# FPGA_Bank_0_Supplies.net
KiCad netlist of a schematic drawn in Altium Designer
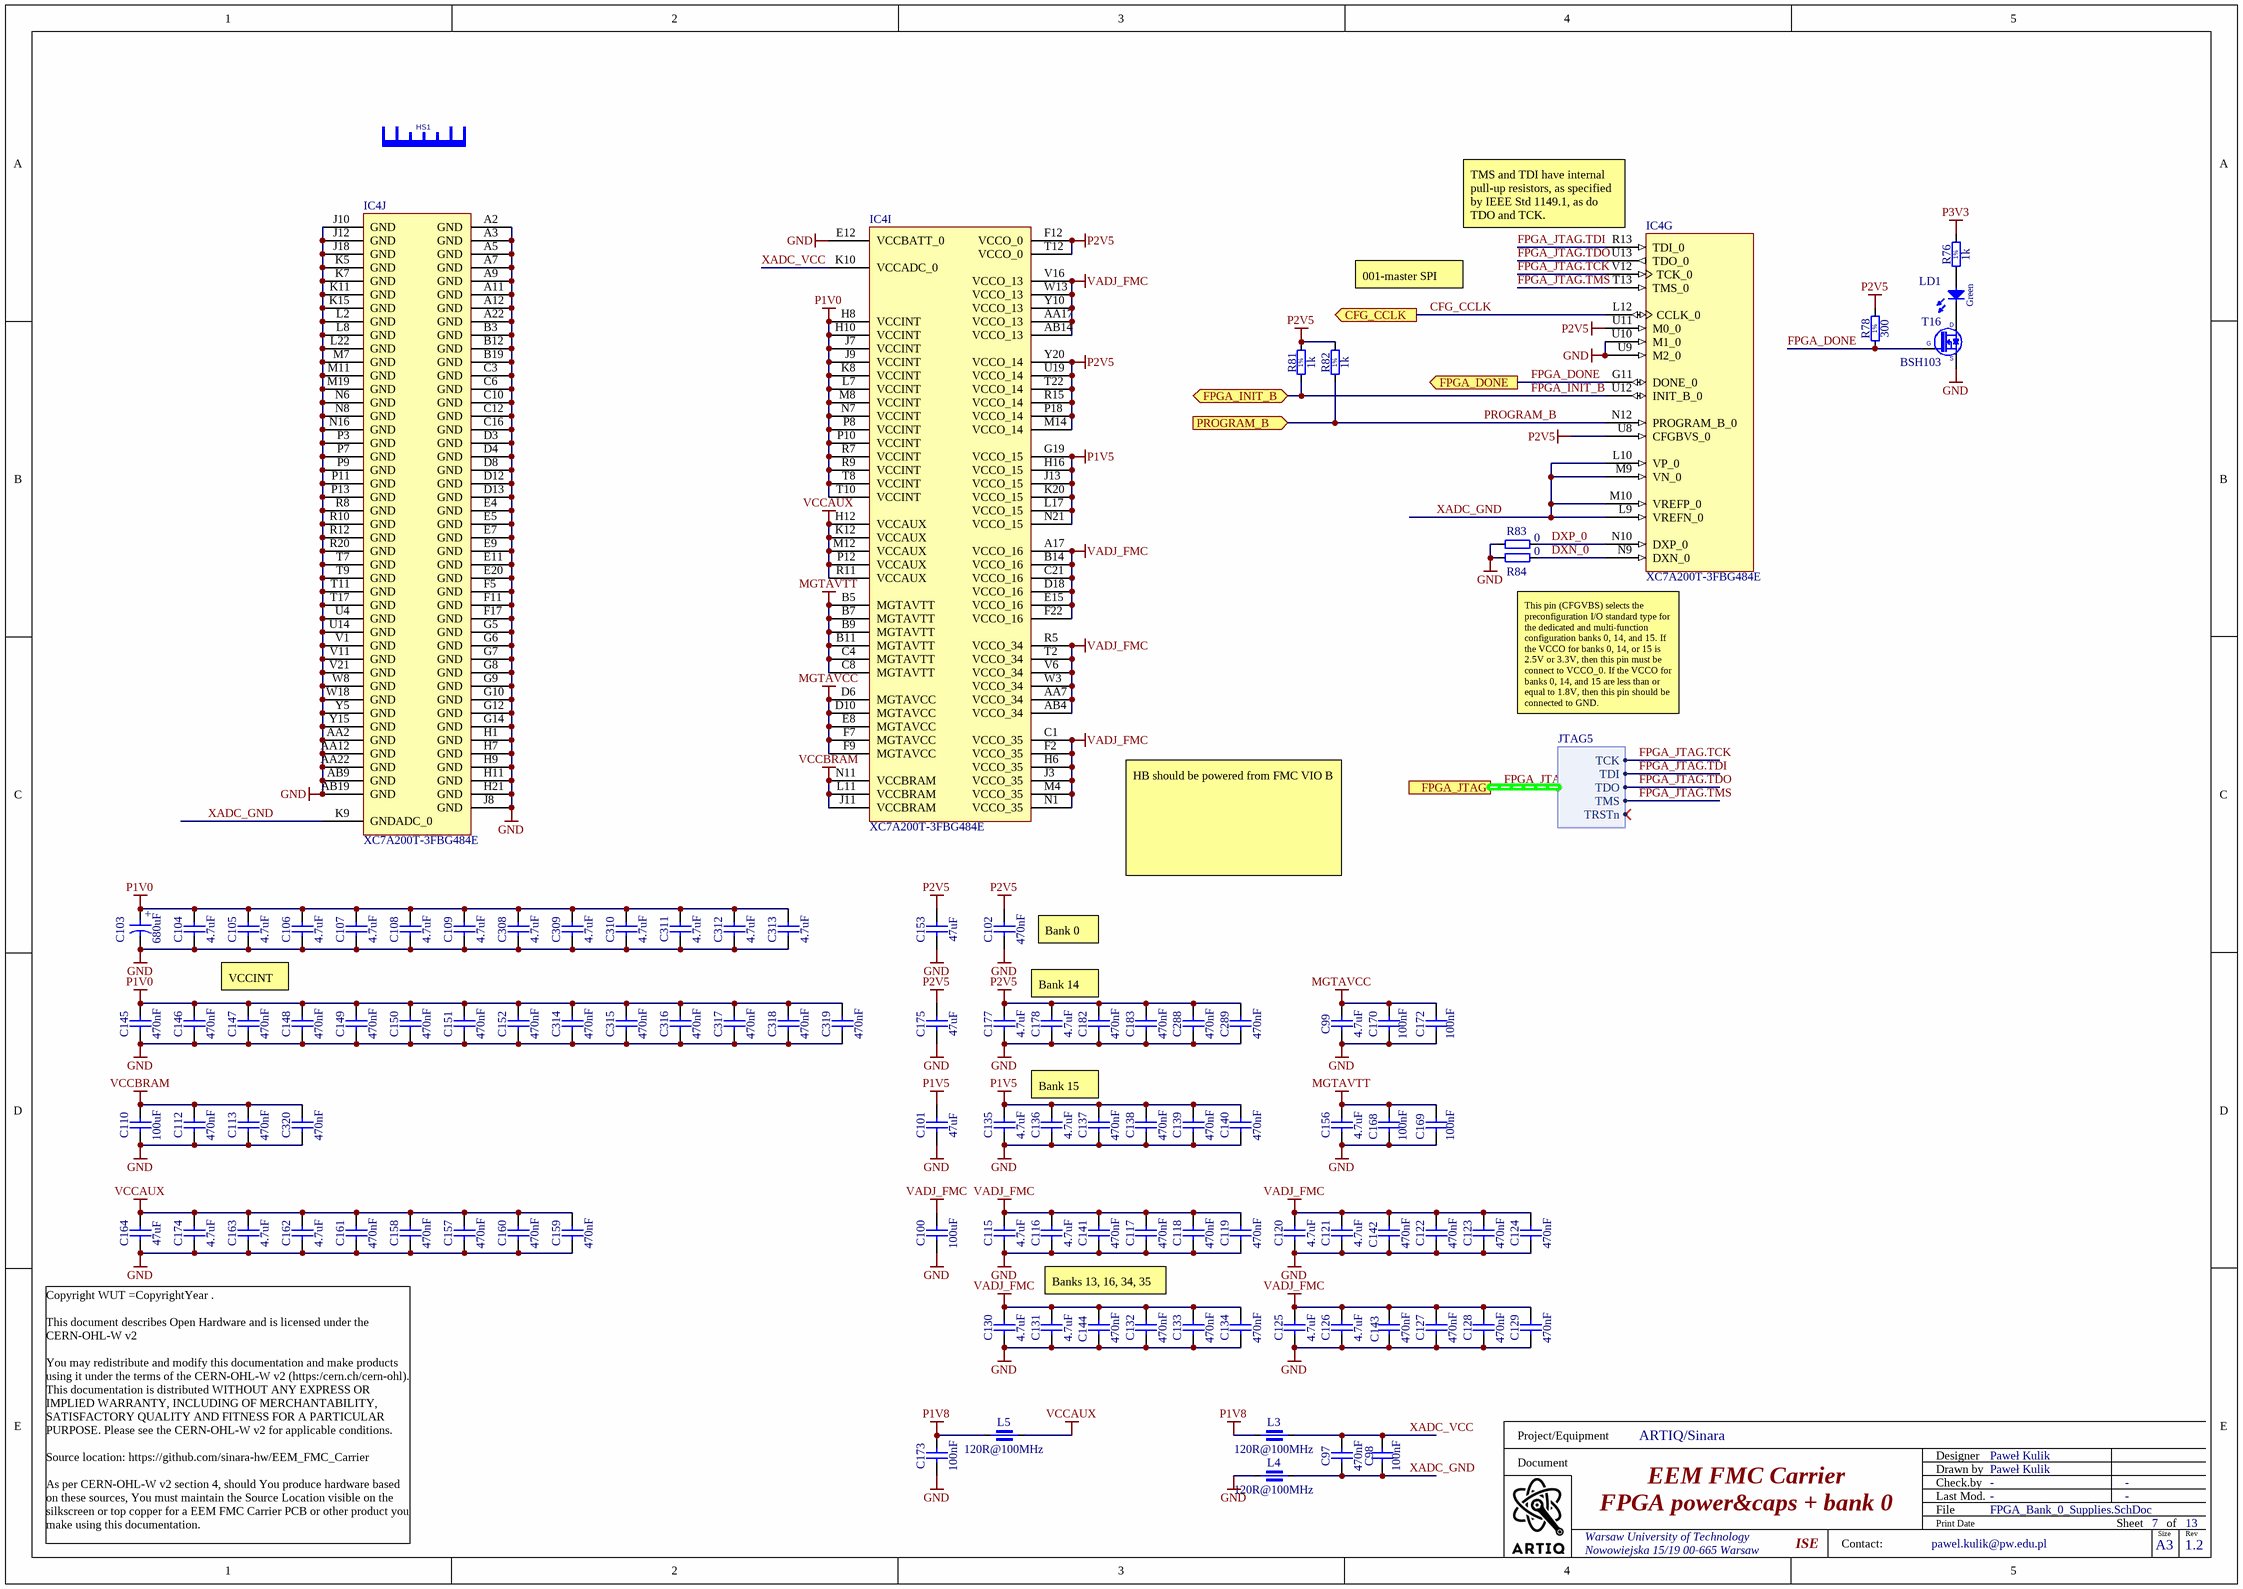
[diagram p0: FPGA_Bank_0_Supplies.SchDoc]

(export (version "E")
  (design (tool "Eeschema 10.0.6"))
  (components
    (comp (ref "C97")
      (value "470nF")
      (footprint "CAPC0603X33N")
      (description "Non-polarised capacitor")
      (fields
        (field (name "PART NUMBER") "CC0201_470NF_4V_20%_X5R")
        (field (name "VOLTAGE") "4V")
        (field (name "AUTHOR") "CERN DEM JLC")
      )
      (libsource (lib "Capacitors") (part "Capacitor - non polarized"))
    )
    (comp (ref "C98")
      (value "100nF")
      (footprint "CAPC0603X33N")
      (description "Non-polarised capacitor")
      (fields
        (field (name "PART NUMBER") "CC0201_100NF_6.3V_10%_X5R")
        (field (name "VOLTAGE") "6.3V")
        (field (name "AUTHOR") "CERN DEM JLC")
      )
      (libsource (lib "Capacitors") (part "Capacitor - non polarized"))
    )
    (comp (ref "C99")
      (value "4.7uF")
      (footprint "CAPC1005X55N")
      (description "Non-polarised capacitor")
      (fields
        (field (name "PART NUMBER") "CC0402_4.7UF_6.3V_20%_X5R")
        (field (name "VOLTAGE") "6.3V")
        (field (name "AUTHOR") "CERN DEM JLC")
      )
      (libsource (lib "Capacitors") (part "Capacitor - non polarized"))
    )
    (comp (ref "C100")
      (value "100uF")
      (footprint "CAPC3216X180N")
      (description "Non-polarised capacitor")
      (fields
        (field (name "PART NUMBER") "CC1206_100UF_6.3V_20%_X5R")
        (field (name "VOLTAGE") "6.3V")
        (field (name "AUTHOR") "CERN DEM JLC")
      )
      (libsource (lib "Capacitors") (part "Capacitor - non polarized"))
    )
    (comp (ref "C101")
      (value "47uF")
      (footprint "CAPC1608X100N")
      (description "Non-polarised capacitor")
      (fields
        (field (name "PART NUMBER") "CC0603_47UF_6.3V_20%_X5R")
        (field (name "VOLTAGE") "6.3V")
        (field (name "AUTHOR") "CERN DEM JLC")
      )
      (libsource (lib "Capacitors") (part "Capacitor - non polarized"))
    )
    (comp (ref "C102")
      (value "470nF")
      (footprint "CAPC0603X33N")
      (description "Non-polarised capacitor")
      (fields
        (field (name "PART NUMBER") "CC0201_470NF_4V_20%_X5R")
        (field (name "VOLTAGE") "4V")
        (field (name "AUTHOR") "CERN DEM JLC")
      )
      (libsource (lib "Capacitors") (part "Capacitor - non polarized"))
    )
    (comp (ref "C103")
      (value "680uF")
      (footprint "CAPMP7343X430N")
      (description "Polarised capacitor")
      (fields
        (field (name "PART NUMBER") "CTE7343-43_680UF_6.3V_10%_LESR0018_AVX_TPM")
        (field (name "VOLTAGE") "6.3V")
        (field (name "AUTHOR") "CERN DEM JLC")
      )
      (libsource (lib "Capacitors") (part "Capacitor - polarized"))
    )
    (comp (ref "C104")
      (value "4.7uF")
      (footprint "CAPC1005X55N")
      (description "Non-polarised capacitor")
      (fields
        (field (name "MANUFACTURER") "GENERIC")
        (field (name "PART NUMBER") "CC0402_4.7UF_6.3V_20%_X5R")
        (field (name "AUTHOR") "CERN DEM JLC")
      )
      (libsource (lib "Capacitors") (part "Capacitor - non polarized"))
    )
    (comp (ref "C105")
      (value "4.7uF")
      (footprint "CAPC1005X55N")
      (description "Non-polarised capacitor")
      (fields
        (field (name "MANUFACTURER") "GENERIC")
        (field (name "PART NUMBER") "CC0402_4.7UF_6.3V_20%_X5R")
        (field (name "AUTHOR") "CERN DEM JLC")
      )
      (libsource (lib "Capacitors") (part "Capacitor - non polarized"))
    )
    (comp (ref "C106")
      (value "4.7uF")
      (footprint "CAPC1005X55N")
      (description "Non-polarised capacitor")
      (fields
        (field (name "MANUFACTURER") "GENERIC")
        (field (name "PART NUMBER") "CC0402_4.7UF_6.3V_20%_X5R")
        (field (name "AUTHOR") "CERN DEM JLC")
      )
      (libsource (lib "Capacitors") (part "Capacitor - non polarized"))
    )
    (comp (ref "C107")
      (value "4.7uF")
      (footprint "CAPC1005X55N")
      (description "Non-polarised capacitor")
      (fields
        (field (name "MANUFACTURER") "GENERIC")
        (field (name "PART NUMBER") "CC0402_4.7UF_6.3V_20%_X5R")
        (field (name "AUTHOR") "CERN DEM JLC")
      )
      (libsource (lib "Capacitors") (part "Capacitor - non polarized"))
    )
    (comp (ref "C108")
      (value "4.7uF")
      (footprint "CAPC1005X55N")
      (description "Non-polarised capacitor")
      (fields
        (field (name "MANUFACTURER") "GENERIC")
        (field (name "PART NUMBER") "CC0402_4.7UF_6.3V_20%_X5R")
        (field (name "AUTHOR") "CERN DEM JLC")
      )
      (libsource (lib "Capacitors") (part "Capacitor - non polarized"))
    )
    (comp (ref "C109")
      (value "4.7uF")
      (footprint "CAPC1005X55N")
      (description "Non-polarised capacitor")
      (fields
        (field (name "MANUFACTURER") "GENERIC")
        (field (name "PART NUMBER") "CC0402_4.7UF_6.3V_20%_X5R")
        (field (name "AUTHOR") "CERN DEM JLC")
      )
      (libsource (lib "Capacitors") (part "Capacitor - non polarized"))
    )
    (comp (ref "C110")
      (value "100uF")
      (footprint "CAPC3216X180N")
      (description "Non-polarised capacitor")
      (fields
        (field (name "PART NUMBER") "CC1206_100UF_6.3V_20%_X5R")
        (field (name "VOLTAGE") "6.3V")
        (field (name "AUTHOR") "CERN DEM JLC")
      )
      (libsource (lib "Capacitors") (part "Capacitor - non polarized"))
    )
    (comp (ref "C112")
      (value "470nF")
      (footprint "CAPC0603X33N")
      (description "Non-polarised capacitor")
      (fields
        (field (name "PART NUMBER") "CC0201_470NF_4V_20%_X5R")
        (field (name "VOLTAGE") "4V")
        (field (name "AUTHOR") "CERN DEM JLC")
      )
      (libsource (lib "Capacitors") (part "Capacitor - non polarized"))
    )
    (comp (ref "C113")
      (value "470nF")
      (footprint "CAPC0603X33N")
      (description "Non-polarised capacitor")
      (fields
        (field (name "PART NUMBER") "CC0201_470NF_4V_20%_X5R")
        (field (name "VOLTAGE") "4V")
        (field (name "AUTHOR") "CERN DEM JLC")
      )
      (libsource (lib "Capacitors") (part "Capacitor - non polarized"))
    )
    (comp (ref "C115")
      (value "4.7uF")
      (footprint "CAPC1005X55N")
      (description "Non-polarised capacitor")
      (fields
        (field (name "MANUFACTURER") "GENERIC")
        (field (name "PART NUMBER") "CC0402_4.7UF_6.3V_20%_X5R")
        (field (name "AUTHOR") "CERN DEM JLC")
      )
      (libsource (lib "Capacitors") (part "Capacitor - non polarized"))
    )
    (comp (ref "C116")
      (value "4.7uF")
      (footprint "CAPC1005X55N")
      (description "Non-polarised capacitor")
      (fields
        (field (name "MANUFACTURER") "GENERIC")
        (field (name "PART NUMBER") "CC0402_4.7UF_6.3V_20%_X5R")
        (field (name "AUTHOR") "CERN DEM JLC")
      )
      (libsource (lib "Capacitors") (part "Capacitor - non polarized"))
    )
    (comp (ref "C117")
      (value "470nF")
      (footprint "CAPC0603X33N")
      (description "Non-polarised capacitor")
      (fields
        (field (name "PART NUMBER") "CC0201_470NF_4V_20%_X5R")
        (field (name "VOLTAGE") "4V")
        (field (name "AUTHOR") "CERN DEM JLC")
      )
      (libsource (lib "Capacitors") (part "Capacitor - non polarized"))
    )
    (comp (ref "C118")
      (value "470nF")
      (footprint "CAPC0603X33N")
      (description "Non-polarised capacitor")
      (fields
        (field (name "PART NUMBER") "CC0201_470NF_4V_20%_X5R")
        (field (name "VOLTAGE") "4V")
        (field (name "AUTHOR") "CERN DEM JLC")
      )
      (libsource (lib "Capacitors") (part "Capacitor - non polarized"))
    )
    (comp (ref "C119")
      (value "470nF")
      (footprint "CAPC0603X33N")
      (description "Non-polarised capacitor")
      (fields
        (field (name "PART NUMBER") "CC0201_470NF_4V_20%_X5R")
        (field (name "VOLTAGE") "4V")
        (field (name "AUTHOR") "CERN DEM JLC")
      )
      (libsource (lib "Capacitors") (part "Capacitor - non polarized"))
    )
    (comp (ref "C120")
      (value "4.7uF")
      (footprint "CAPC1005X55N")
      (description "Non-polarised capacitor")
      (fields
        (field (name "MANUFACTURER") "GENERIC")
        (field (name "PART NUMBER") "CC0402_4.7UF_6.3V_20%_X5R")
        (field (name "AUTHOR") "CERN DEM JLC")
      )
      (libsource (lib "Capacitors") (part "Capacitor - non polarized"))
    )
    (comp (ref "C121")
      (value "4.7uF")
      (footprint "CAPC1005X55N")
      (description "Non-polarised capacitor")
      (fields
        (field (name "MANUFACTURER") "GENERIC")
        (field (name "PART NUMBER") "CC0402_4.7UF_6.3V_20%_X5R")
        (field (name "AUTHOR") "CERN DEM JLC")
      )
      (libsource (lib "Capacitors") (part "Capacitor - non polarized"))
    )
    (comp (ref "C122")
      (value "470nF")
      (footprint "CAPC0603X33N")
      (description "Non-polarised capacitor")
      (fields
        (field (name "PART NUMBER") "CC0201_470NF_4V_20%_X5R")
        (field (name "VOLTAGE") "4V")
        (field (name "AUTHOR") "CERN DEM JLC")
      )
      (libsource (lib "Capacitors") (part "Capacitor - non polarized"))
    )
    (comp (ref "C123")
      (value "470nF")
      (footprint "CAPC0603X33N")
      (description "Non-polarised capacitor")
      (fields
        (field (name "PART NUMBER") "CC0201_470NF_4V_20%_X5R")
        (field (name "VOLTAGE") "4V")
        (field (name "AUTHOR") "CERN DEM JLC")
      )
      (libsource (lib "Capacitors") (part "Capacitor - non polarized"))
    )
    (comp (ref "C124")
      (value "470nF")
      (footprint "CAPC0603X33N")
      (description "Non-polarised capacitor")
      (fields
        (field (name "PART NUMBER") "CC0201_470NF_4V_20%_X5R")
        (field (name "VOLTAGE") "4V")
        (field (name "AUTHOR") "CERN DEM JLC")
      )
      (libsource (lib "Capacitors") (part "Capacitor - non polarized"))
    )
    (comp (ref "C125")
      (value "4.7uF")
      (footprint "CAPC1005X55N")
      (description "Non-polarised capacitor")
      (fields
        (field (name "MANUFACTURER") "GENERIC")
        (field (name "PART NUMBER") "CC0402_4.7UF_6.3V_20%_X5R")
        (field (name "AUTHOR") "CERN DEM JLC")
      )
      (libsource (lib "Capacitors") (part "Capacitor - non polarized"))
    )
    (comp (ref "C126")
      (value "4.7uF")
      (footprint "CAPC1005X55N")
      (description "Non-polarised capacitor")
      (fields
        (field (name "MANUFACTURER") "GENERIC")
        (field (name "PART NUMBER") "CC0402_4.7UF_6.3V_20%_X5R")
        (field (name "AUTHOR") "CERN DEM JLC")
      )
      (libsource (lib "Capacitors") (part "Capacitor - non polarized"))
    )
    (comp (ref "C127")
      (value "470nF")
      (footprint "CAPC0603X33N")
      (description "Non-polarised capacitor")
      (fields
        (field (name "PART NUMBER") "CC0201_470NF_4V_20%_X5R")
        (field (name "VOLTAGE") "4V")
        (field (name "AUTHOR") "CERN DEM JLC")
      )
      (libsource (lib "Capacitors") (part "Capacitor - non polarized"))
    )
    (comp (ref "C128")
      (value "470nF")
      (footprint "CAPC0603X33N")
      (description "Non-polarised capacitor")
      (fields
        (field (name "PART NUMBER") "CC0201_470NF_4V_20%_X5R")
        (field (name "VOLTAGE") "4V")
        (field (name "AUTHOR") "CERN DEM JLC")
      )
      (libsource (lib "Capacitors") (part "Capacitor - non polarized"))
    )
    (comp (ref "C129")
      (value "470nF")
      (footprint "CAPC0603X33N")
      (description "Non-polarised capacitor")
      (fields
        (field (name "PART NUMBER") "CC0201_470NF_4V_20%_X5R")
        (field (name "VOLTAGE") "4V")
        (field (name "AUTHOR") "CERN DEM JLC")
      )
      (libsource (lib "Capacitors") (part "Capacitor - non polarized"))
    )
    (comp (ref "C130")
      (value "4.7uF")
      (footprint "CAPC1005X55N")
      (description "Non-polarised capacitor")
      (fields
        (field (name "MANUFACTURER") "GENERIC")
        (field (name "PART NUMBER") "CC0402_4.7UF_6.3V_20%_X5R")
        (field (name "AUTHOR") "CERN DEM JLC")
      )
      (libsource (lib "Capacitors") (part "Capacitor - non polarized"))
    )
    (comp (ref "C131")
      (value "4.7uF")
      (footprint "CAPC1005X55N")
      (description "Non-polarised capacitor")
      (fields
        (field (name "MANUFACTURER") "GENERIC")
        (field (name "PART NUMBER") "CC0402_4.7UF_6.3V_20%_X5R")
        (field (name "AUTHOR") "CERN DEM JLC")
      )
      (libsource (lib "Capacitors") (part "Capacitor - non polarized"))
    )
    (comp (ref "C132")
      (value "470nF")
      (footprint "CAPC0603X33N")
      (description "Non-polarised capacitor")
      (fields
        (field (name "PART NUMBER") "CC0201_470NF_4V_20%_X5R")
        (field (name "VOLTAGE") "4V")
        (field (name "AUTHOR") "CERN DEM JLC")
      )
      (libsource (lib "Capacitors") (part "Capacitor - non polarized"))
    )
    (comp (ref "C133")
      (value "470nF")
      (footprint "CAPC0603X33N")
      (description "Non-polarised capacitor")
      (fields
        (field (name "PART NUMBER") "CC0201_470NF_4V_20%_X5R")
        (field (name "VOLTAGE") "4V")
        (field (name "AUTHOR") "CERN DEM JLC")
      )
      (libsource (lib "Capacitors") (part "Capacitor - non polarized"))
    )
    (comp (ref "C134")
      (value "470nF")
      (footprint "CAPC0603X33N")
      (description "Non-polarised capacitor")
      (fields
        (field (name "PART NUMBER") "CC0201_470NF_4V_20%_X5R")
        (field (name "VOLTAGE") "4V")
        (field (name "AUTHOR") "CERN DEM JLC")
      )
      (libsource (lib "Capacitors") (part "Capacitor - non polarized"))
    )
    (comp (ref "C135")
      (value "4.7uF")
      (footprint "CAPC1005X55N")
      (description "Non-polarised capacitor")
      (fields
        (field (name "MANUFACTURER") "GENERIC")
        (field (name "PART NUMBER") "CC0402_4.7UF_6.3V_20%_X5R")
        (field (name "AUTHOR") "CERN DEM JLC")
      )
      (libsource (lib "Capacitors") (part "Capacitor - non polarized"))
    )
    (comp (ref "C136")
      (value "4.7uF")
      (footprint "CAPC1005X55N")
      (description "Non-polarised capacitor")
      (fields
        (field (name "MANUFACTURER") "GENERIC")
        (field (name "PART NUMBER") "CC0402_4.7UF_6.3V_20%_X5R")
        (field (name "AUTHOR") "CERN DEM JLC")
      )
      (libsource (lib "Capacitors") (part "Capacitor - non polarized"))
    )
    (comp (ref "C137")
      (value "470nF")
      (footprint "CAPC0603X33N")
      (description "Non-polarised capacitor")
      (fields
        (field (name "PART NUMBER") "CC0201_470NF_4V_20%_X5R")
        (field (name "VOLTAGE") "4V")
        (field (name "AUTHOR") "CERN DEM JLC")
      )
      (libsource (lib "Capacitors") (part "Capacitor - non polarized"))
    )
    (comp (ref "C138")
      (value "470nF")
      (footprint "CAPC0603X33N")
      (description "Non-polarised capacitor")
      (fields
        (field (name "PART NUMBER") "CC0201_470NF_4V_20%_X5R")
        (field (name "VOLTAGE") "4V")
        (field (name "AUTHOR") "CERN DEM JLC")
      )
      (libsource (lib "Capacitors") (part "Capacitor - non polarized"))
    )
    (comp (ref "C139")
      (value "470nF")
      (footprint "CAPC0603X33N")
      (description "Non-polarised capacitor")
      (fields
        (field (name "PART NUMBER") "CC0201_470NF_4V_20%_X5R")
        (field (name "VOLTAGE") "4V")
        (field (name "AUTHOR") "CERN DEM JLC")
      )
      (libsource (lib "Capacitors") (part "Capacitor - non polarized"))
    )
    (comp (ref "C140")
      (value "470nF")
      (footprint "CAPC0603X33N")
      (description "Non-polarised capacitor")
      (fields
        (field (name "PART NUMBER") "CC0201_470NF_4V_20%_X5R")
        (field (name "VOLTAGE") "4V")
        (field (name "AUTHOR") "CERN DEM JLC")
      )
      (libsource (lib "Capacitors") (part "Capacitor - non polarized"))
    )
    (comp (ref "C141")
      (value "470nF")
      (footprint "CAPC0603X33N")
      (description "Non-polarised capacitor")
      (fields
        (field (name "PART NUMBER") "CC0201_470NF_4V_20%_X5R")
        (field (name "VOLTAGE") "4V")
        (field (name "AUTHOR") "CERN DEM JLC")
      )
      (libsource (lib "Capacitors") (part "Capacitor - non polarized"))
    )
    (comp (ref "C142")
      (value "470nF")
      (footprint "CAPC0603X33N")
      (description "Non-polarised capacitor")
      (fields
        (field (name "PART NUMBER") "CC0201_470NF_4V_20%_X5R")
        (field (name "VOLTAGE") "4V")
        (field (name "AUTHOR") "CERN DEM JLC")
      )
      (libsource (lib "Capacitors") (part "Capacitor - non polarized"))
    )
    (comp (ref "C143")
      (value "470nF")
      (footprint "CAPC0603X33N")
      (description "Non-polarised capacitor")
      (fields
        (field (name "PART NUMBER") "CC0201_470NF_4V_20%_X5R")
        (field (name "VOLTAGE") "4V")
        (field (name "AUTHOR") "CERN DEM JLC")
      )
      (libsource (lib "Capacitors") (part "Capacitor - non polarized"))
    )
    (comp (ref "C144")
      (value "470nF")
      (footprint "CAPC0603X33N")
      (description "Non-polarised capacitor")
      (fields
        (field (name "PART NUMBER") "CC0201_470NF_4V_20%_X5R")
        (field (name "VOLTAGE") "4V")
        (field (name "AUTHOR") "CERN DEM JLC")
      )
      (libsource (lib "Capacitors") (part "Capacitor - non polarized"))
    )
    (comp (ref "C145")
      (value "470nF")
      (footprint "CAPC0603X33N")
      (description "Non-polarised capacitor")
      (fields
        (field (name "PART NUMBER") "CC0201_470NF_4V_20%_X5R")
        (field (name "VOLTAGE") "4V")
        (field (name "AUTHOR") "CERN DEM JLC")
      )
      (libsource (lib "Capacitors") (part "Capacitor - non polarized"))
    )
    (comp (ref "C146")
      (value "470nF")
      (footprint "CAPC0603X33N")
      (description "Non-polarised capacitor")
      (fields
        (field (name "PART NUMBER") "CC0201_470NF_4V_20%_X5R")
        (field (name "VOLTAGE") "4V")
        (field (name "AUTHOR") "CERN DEM JLC")
      )
      (libsource (lib "Capacitors") (part "Capacitor - non polarized"))
    )
    (comp (ref "C147")
      (value "470nF")
      (footprint "CAPC0603X33N")
      (description "Non-polarised capacitor")
      (fields
        (field (name "PART NUMBER") "CC0201_470NF_4V_20%_X5R")
        (field (name "VOLTAGE") "4V")
        (field (name "AUTHOR") "CERN DEM JLC")
      )
      (libsource (lib "Capacitors") (part "Capacitor - non polarized"))
    )
    (comp (ref "C148")
      (value "470nF")
      (footprint "CAPC0603X33N")
      (description "Non-polarised capacitor")
      (fields
        (field (name "PART NUMBER") "CC0201_470NF_4V_20%_X5R")
        (field (name "VOLTAGE") "4V")
        (field (name "AUTHOR") "CERN DEM JLC")
      )
      (libsource (lib "Capacitors") (part "Capacitor - non polarized"))
    )
    (comp (ref "C149")
      (value "470nF")
      (footprint "CAPC0603X33N")
      (description "Non-polarised capacitor")
      (fields
        (field (name "PART NUMBER") "CC0201_470NF_4V_20%_X5R")
        (field (name "VOLTAGE") "4V")
        (field (name "AUTHOR") "CERN DEM JLC")
      )
      (libsource (lib "Capacitors") (part "Capacitor - non polarized"))
    )
    (comp (ref "C150")
      (value "470nF")
      (footprint "CAPC0603X33N")
      (description "Non-polarised capacitor")
      (fields
        (field (name "PART NUMBER") "CC0201_470NF_4V_20%_X5R")
        (field (name "VOLTAGE") "4V")
        (field (name "AUTHOR") "CERN DEM JLC")
      )
      (libsource (lib "Capacitors") (part "Capacitor - non polarized"))
    )
    (comp (ref "C151")
      (value "470nF")
      (footprint "CAPC0603X33N")
      (description "Non-polarised capacitor")
      (fields
        (field (name "PART NUMBER") "CC0201_470NF_4V_20%_X5R")
        (field (name "VOLTAGE") "4V")
        (field (name "AUTHOR") "CERN DEM JLC")
      )
      (libsource (lib "Capacitors") (part "Capacitor - non polarized"))
    )
    (comp (ref "C152")
      (value "470nF")
      (footprint "CAPC0603X33N")
      (description "Non-polarised capacitor")
      (fields
        (field (name "PART NUMBER") "CC0201_470NF_4V_20%_X5R")
        (field (name "VOLTAGE") "4V")
        (field (name "AUTHOR") "CERN DEM JLC")
      )
      (libsource (lib "Capacitors") (part "Capacitor - non polarized"))
    )
    (comp (ref "C153")
      (value "47uF")
      (footprint "CAPC1608X100N")
      (description "Non-polarised capacitor")
      (fields
        (field (name "PART NUMBER") "CC0603_47UF_6.3V_20%_X5R")
        (field (name "VOLTAGE") "6.3V")
        (field (name "AUTHOR") "CERN DEM JLC")
      )
      (libsource (lib "Capacitors") (part "Capacitor - non polarized"))
    )
    (comp (ref "C156")
      (value "4.7uF")
      (footprint "CAPC1005X55N")
      (description "Non-polarised capacitor")
      (fields
        (field (name "PART NUMBER") "CC0402_4.7UF_6.3V_20%_X5R")
        (field (name "VOLTAGE") "6.3V")
        (field (name "AUTHOR") "CERN DEM JLC")
      )
      (libsource (lib "Capacitors") (part "Capacitor - non polarized"))
    )
    (comp (ref "C157")
      (value "470nF")
      (footprint "CAPC0603X33N")
      (description "Non-polarised capacitor")
      (fields
        (field (name "PART NUMBER") "CC0201_470NF_4V_20%_X5R")
        (field (name "VOLTAGE") "4V")
        (field (name "AUTHOR") "CERN DEM JLC")
      )
      (libsource (lib "Capacitors") (part "Capacitor - non polarized"))
    )
    (comp (ref "C158")
      (value "470nF")
      (footprint "CAPC0603X33N")
      (description "Non-polarised capacitor")
      (fields
        (field (name "PART NUMBER") "CC0201_470NF_4V_20%_X5R")
        (field (name "VOLTAGE") "4V")
        (field (name "AUTHOR") "CERN DEM JLC")
      )
      (libsource (lib "Capacitors") (part "Capacitor - non polarized"))
    )
    (comp (ref "C159")
      (value "470nF")
      (footprint "CAPC0603X33N")
      (description "Non-polarised capacitor")
      (fields
        (field (name "PART NUMBER") "CC0201_470NF_4V_20%_X5R")
        (field (name "VOLTAGE") "4V")
        (field (name "AUTHOR") "CERN DEM JLC")
      )
      (libsource (lib "Capacitors") (part "Capacitor - non polarized"))
    )
    (comp (ref "C160")
      (value "470nF")
      (footprint "CAPC0603X33N")
      (description "Non-polarised capacitor")
      (fields
        (field (name "PART NUMBER") "CC0201_470NF_4V_20%_X5R")
        (field (name "VOLTAGE") "4V")
        (field (name "AUTHOR") "CERN DEM JLC")
      )
      (libsource (lib "Capacitors") (part "Capacitor - non polarized"))
    )
    (comp (ref "C161")
      (value "470nF")
      (footprint "CAPC0603X33N")
      (description "Non-polarised capacitor")
      (fields
        (field (name "PART NUMBER") "CC0201_470NF_4V_20%_X5R")
        (field (name "VOLTAGE") "4V")
        (field (name "AUTHOR") "CERN DEM JLC")
      )
      (libsource (lib "Capacitors") (part "Capacitor - non polarized"))
    )
    (comp (ref "C162")
      (value "4.7uF")
      (footprint "CAPC1005X55N")
      (description "Non-polarised capacitor")
      (fields
        (field (name "MANUFACTURER") "GENERIC")
        (field (name "PART NUMBER") "CC0402_4.7UF_6.3V_20%_X5R")
        (field (name "AUTHOR") "CERN DEM JLC")
      )
      (libsource (lib "Capacitors") (part "Capacitor - non polarized"))
    )
    (comp (ref "C163")
      (value "4.7uF")
      (footprint "CAPC1005X55N")
      (description "Non-polarised capacitor")
      (fields
        (field (name "MANUFACTURER") "GENERIC")
        (field (name "PART NUMBER") "CC0402_4.7UF_6.3V_20%_X5R")
        (field (name "AUTHOR") "CERN DEM JLC")
      )
      (libsource (lib "Capacitors") (part "Capacitor - non polarized"))
    )
    (comp (ref "C164")
      (value "47uF")
      (footprint "CAPC1608X100N")
      (description "Non-polarised capacitor")
      (fields
        (field (name "PART NUMBER") "CC0603_47UF_6.3V_20%_X5R")
        (field (name "VOLTAGE") "6.3V")
        (field (name "AUTHOR") "CERN DEM JLC")
      )
      (libsource (lib "Capacitors") (part "Capacitor - non polarized"))
    )
    (comp (ref "C168")
      (value "100nF")
      (footprint "CAPC0603X33N")
      (description "Non-polarised capacitor")
      (fields
        (field (name "PART NUMBER") "CC0201_100NF_6.3V_10%_X5R")
        (field (name "VOLTAGE") "6.3V")
        (field (name "AUTHOR") "CERN DEM JLC")
      )
      (libsource (lib "Capacitors") (part "Capacitor - non polarized"))
    )
    (comp (ref "C169")
      (value "100nF")
      (footprint "CAPC0603X33N")
      (description "Non-polarised capacitor")
      (fields
        (field (name "PART NUMBER") "CC0201_100NF_6.3V_10%_X5R")
        (field (name "VOLTAGE") "6.3V")
        (field (name "AUTHOR") "CERN DEM JLC")
      )
      (libsource (lib "Capacitors") (part "Capacitor - non polarized"))
    )
    (comp (ref "C170")
      (value "100nF")
      (footprint "CAPC0603X33N")
      (description "Non-polarised capacitor")
      (fields
        (field (name "PART NUMBER") "CC0201_100NF_6.3V_10%_X5R")
        (field (name "VOLTAGE") "6.3V")
        (field (name "AUTHOR") "CERN DEM JLC")
      )
      (libsource (lib "Capacitors") (part "Capacitor - non polarized"))
    )
    (comp (ref "C172")
      (value "100nF")
      (footprint "CAPC0603X33N")
      (description "Non-polarised capacitor")
      (fields
        (field (name "PART NUMBER") "CC0201_100NF_6.3V_10%_X5R")
        (field (name "VOLTAGE") "6.3V")
        (field (name "AUTHOR") "CERN DEM JLC")
      )
      (libsource (lib "Capacitors") (part "Capacitor - non polarized"))
    )
    (comp (ref "C173")
      (value "100nF")
      (footprint "CAPC0603X33N")
      (description "Non-polarised capacitor")
      (fields
        (field (name "PART NUMBER") "CC0201_100NF_6.3V_10%_X5R")
        (field (name "VOLTAGE") "6.3V")
        (field (name "AUTHOR") "CERN DEM JLC")
      )
      (libsource (lib "Capacitors") (part "Capacitor - non polarized"))
    )
    (comp (ref "C174")
      (value "4.7uF")
      (footprint "CAPC1005X55N")
      (description "Non-polarised capacitor")
      (fields
        (field (name "PART NUMBER") "CC0402_4.7UF_6.3V_20%_X5R")
        (field (name "VOLTAGE") "6.3V")
        (field (name "AUTHOR") "CERN DEM JLC")
      )
      (libsource (lib "Capacitors") (part "Capacitor - non polarized"))
    )
    (comp (ref "C175")
      (value "47uF")
      (footprint "CAPC1608X100N")
      (description "Non-polarised capacitor")
      (fields
        (field (name "PART NUMBER") "CC0603_47UF_6.3V_20%_X5R")
        (field (name "VOLTAGE") "6.3V")
        (field (name "AUTHOR") "CERN DEM JLC")
      )
      (libsource (lib "Capacitors") (part "Capacitor - non polarized"))
    )
    (comp (ref "C177")
      (value "4.7uF")
      (footprint "CAPC1005X55N")
      (description "Non-polarised capacitor")
      (fields
        (field (name "MANUFACTURER") "GENERIC")
        (field (name "PART NUMBER") "CC0402_4.7UF_6.3V_20%_X5R")
        (field (name "AUTHOR") "CERN DEM JLC")
      )
      (libsource (lib "Capacitors") (part "Capacitor - non polarized"))
    )
    (comp (ref "C178")
      (value "4.7uF")
      (footprint "CAPC1005X55N")
      (description "Non-polarised capacitor")
      (fields
        (field (name "MANUFACTURER") "GENERIC")
        (field (name "PART NUMBER") "CC0402_4.7UF_6.3V_20%_X5R")
        (field (name "AUTHOR") "CERN DEM JLC")
      )
      (libsource (lib "Capacitors") (part "Capacitor - non polarized"))
    )
    (comp (ref "C182")
      (value "470nF")
      (footprint "CAPC0603X33N")
      (description "Non-polarised capacitor")
      (fields
        (field (name "PART NUMBER") "CC0201_470NF_4V_20%_X5R")
        (field (name "VOLTAGE") "4V")
        (field (name "AUTHOR") "CERN DEM JLC")
      )
      (libsource (lib "Capacitors") (part "Capacitor - non polarized"))
    )
    (comp (ref "C183")
      (value "470nF")
      (footprint "CAPC0603X33N")
      (description "Non-polarised capacitor")
      (fields
        (field (name "PART NUMBER") "CC0201_470NF_4V_20%_X5R")
        (field (name "VOLTAGE") "4V")
        (field (name "AUTHOR") "CERN DEM JLC")
      )
      (libsource (lib "Capacitors") (part "Capacitor - non polarized"))
    )
    (comp (ref "C288")
      (value "470nF")
      (footprint "CAPC0603X33N")
      (description "Non-polarised capacitor")
      (fields
        (field (name "PART NUMBER") "CC0201_470NF_4V_20%_X5R")
        (field (name "VOLTAGE") "4V")
        (field (name "AUTHOR") "CERN DEM JLC")
      )
      (libsource (lib "Capacitors") (part "Capacitor - non polarized"))
    )
    (comp (ref "C289")
      (value "470nF")
      (footprint "CAPC0603X33N")
      (description "Non-polarised capacitor")
      (fields
        (field (name "PART NUMBER") "CC0201_470NF_4V_20%_X5R")
        (field (name "VOLTAGE") "4V")
        (field (name "AUTHOR") "CERN DEM JLC")
      )
      (libsource (lib "Capacitors") (part "Capacitor - non polarized"))
    )
    (comp (ref "C308")
      (value "4.7uF")
      (footprint "CAPC1005X55N")
      (description "Non-polarised capacitor")
      (fields
        (field (name "MANUFACTURER") "GENERIC")
        (field (name "PART NUMBER") "CC0402_4.7UF_6.3V_20%_X5R")
        (field (name "AUTHOR") "CERN DEM JLC")
      )
      (libsource (lib "Capacitors") (part "Capacitor - non polarized"))
    )
    (comp (ref "C309")
      (value "4.7uF")
      (footprint "CAPC1005X55N")
      (description "Non-polarised capacitor")
      (fields
        (field (name "MANUFACTURER") "GENERIC")
        (field (name "PART NUMBER") "CC0402_4.7UF_6.3V_20%_X5R")
        (field (name "AUTHOR") "CERN DEM JLC")
      )
      (libsource (lib "Capacitors") (part "Capacitor - non polarized"))
    )
    (comp (ref "C310")
      (value "4.7uF")
      (footprint "CAPC1005X55N")
      (description "Non-polarised capacitor")
      (fields
        (field (name "MANUFACTURER") "GENERIC")
        (field (name "PART NUMBER") "CC0402_4.7UF_6.3V_20%_X5R")
        (field (name "AUTHOR") "CERN DEM JLC")
      )
      (libsource (lib "Capacitors") (part "Capacitor - non polarized"))
    )
    (comp (ref "C311")
      (value "4.7uF")
      (footprint "CAPC1005X55N")
      (description "Non-polarised capacitor")
      (fields
        (field (name "MANUFACTURER") "GENERIC")
        (field (name "PART NUMBER") "CC0402_4.7UF_6.3V_20%_X5R")
        (field (name "AUTHOR") "CERN DEM JLC")
      )
      (libsource (lib "Capacitors") (part "Capacitor - non polarized"))
    )
    (comp (ref "C312")
      (value "4.7uF")
      (footprint "CAPC1005X55N")
      (description "Non-polarised capacitor")
      (fields
        (field (name "MANUFACTURER") "GENERIC")
        (field (name "PART NUMBER") "CC0402_4.7UF_6.3V_20%_X5R")
        (field (name "AUTHOR") "CERN DEM JLC")
      )
      (libsource (lib "Capacitors") (part "Capacitor - non polarized"))
    )
    (comp (ref "C313")
      (value "4.7uF")
      (footprint "CAPC1005X55N")
      (description "Non-polarised capacitor")
      (fields
        (field (name "MANUFACTURER") "GENERIC")
        (field (name "PART NUMBER") "CC0402_4.7UF_6.3V_20%_X5R")
        (field (name "AUTHOR") "CERN DEM JLC")
      )
      (libsource (lib "Capacitors") (part "Capacitor - non polarized"))
    )
    (comp (ref "C314")
      (value "470nF")
      (footprint "CAPC0603X33N")
      (description "Non-polarised capacitor")
      (fields
        (field (name "PART NUMBER") "CC0201_470NF_4V_20%_X5R")
        (field (name "VOLTAGE") "4V")
        (field (name "AUTHOR") "CERN DEM JLC")
      )
      (libsource (lib "Capacitors") (part "Capacitor - non polarized"))
    )
    (comp (ref "C315")
      (value "470nF")
      (footprint "CAPC0603X33N")
      (description "Non-polarised capacitor")
      (fields
        (field (name "PART NUMBER") "CC0201_470NF_4V_20%_X5R")
        (field (name "VOLTAGE") "4V")
        (field (name "AUTHOR") "CERN DEM JLC")
      )
      (libsource (lib "Capacitors") (part "Capacitor - non polarized"))
    )
    (comp (ref "C316")
      (value "470nF")
      (footprint "CAPC0603X33N")
      (description "Non-polarised capacitor")
      (fields
        (field (name "PART NUMBER") "CC0201_470NF_4V_20%_X5R")
        (field (name "VOLTAGE") "4V")
        (field (name "AUTHOR") "CERN DEM JLC")
      )
      (libsource (lib "Capacitors") (part "Capacitor - non polarized"))
    )
    (comp (ref "C317")
      (value "470nF")
      (footprint "CAPC0603X33N")
      (description "Non-polarised capacitor")
      (fields
        (field (name "PART NUMBER") "CC0201_470NF_4V_20%_X5R")
        (field (name "VOLTAGE") "4V")
        (field (name "AUTHOR") "CERN DEM JLC")
      )
      (libsource (lib "Capacitors") (part "Capacitor - non polarized"))
    )
    (comp (ref "C318")
      (value "470nF")
      (footprint "CAPC0603X33N")
      (description "Non-polarised capacitor")
      (fields
        (field (name "PART NUMBER") "CC0201_470NF_4V_20%_X5R")
        (field (name "VOLTAGE") "4V")
        (field (name "AUTHOR") "CERN DEM JLC")
      )
      (libsource (lib "Capacitors") (part "Capacitor - non polarized"))
    )
    (comp (ref "C319")
      (value "470nF")
      (footprint "CAPC0603X33N")
      (description "Non-polarised capacitor")
      (fields
        (field (name "PART NUMBER") "CC0201_470NF_4V_20%_X5R")
        (field (name "VOLTAGE") "4V")
        (field (name "AUTHOR") "CERN DEM JLC")
      )
      (libsource (lib "Capacitors") (part "Capacitor - non polarized"))
    )
    (comp (ref "C320")
      (value "470nF")
      (footprint "CAPC0603X33N")
      (description "Non-polarised capacitor")
      (fields
        (field (name "PART NUMBER") "CC0201_470NF_4V_20%_X5R")
        (field (name "VOLTAGE") "4V")
        (field (name "AUTHOR") "CERN DEM JLC")
      )
      (libsource (lib "Capacitors") (part "Capacitor - non polarized"))
    )
    (comp (ref "HS1")
      (value "RADIAN_FI23")
      (footprint "RADIAN_FI23")
      (description "Heat Sink Without Pad")
      (fields
        (field (name "MANUFACTURER") "Radian Thermal Products, Inc.")
        (field (name "MANUFACTURER PART NUMBER") "FI23+BU+T725")
      )
      (libsource (lib "Schlib1") (part "RADIAN_FI23"))
    )
    (comp (ref "IC4")
      (value "XC7A200T-3FBG484E")
      (footprint "BGA484C100P22X22_2300X2300X254")
      (description "Artix-7 FPGA, 285 User I/Os, 4 GTP, 484-Ball BGA, Pb-Free")
      (libsource (lib "Integrated_Library_LOADER") (part "XC7A200T-3FBG484E"))
    )
    (comp (ref "L3")
      (value "120R@100MHz")
      (footprint "INDC1608X65N")
      (fields
        (field (name "PART NUMBER") "IND0603_MURATA_BLM18SG121TN1D")
        (field (name "POWER") "3A")
        (field (name "MANUFACTURER") "MURATA")
        (field (name "AUTHOR") "CERN DEM JLC")
      )
      (libsource (lib "Inductors & Transformers") (part "Ferrite Bead"))
    )
    (comp (ref "L4")
      (value "120R@100MHz")
      (footprint "INDC1608X65N")
      (fields
        (field (name "PART NUMBER") "IND0603_MURATA_BLM18SG121TN1D")
        (field (name "POWER") "3A")
        (field (name "MANUFACTURER") "MURATA")
        (field (name "AUTHOR") "CERN DEM JLC")
      )
      (libsource (lib "Inductors & Transformers") (part "Ferrite Bead"))
    )
    (comp (ref "L5")
      (value "120R@100MHz")
      (footprint "INDC1608X65N")
      (fields
        (field (name "PART NUMBER") "IND0603_MURATA_BLM18SG121TN1D")
        (field (name "POWER") "3A")
        (field (name "MANUFACTURER") "MURATA")
        (field (name "AUTHOR") "CERN DEM JLC")
      )
      (libsource (lib "Inductors & Transformers") (part "Ferrite Bead"))
    )
    (comp (ref "LD1")
      (value "Green")
      (footprint "LED_KINGBRIGHT_KPH-1608CGCK")
      (description "LED Green 1C 2A")
      (fields
        (field (name "MANUFACTURER PART NUMBER") "KPH-1608CGCK")
        (field (name "PART NUMBER") "LED_KINGBRIGHT_KPH-1608CGCK")
        (field (name "AUTHOR") "CERN DEM JLC")
      )
      (libsource (lib "ICs And Semiconductors") (part "LED Green 1C 2A"))
    )
    (comp (ref "R76")
      (value "1k")
      (footprint "RESC1005X40N")
      (description "Resistor - 1%")
      (fields
        (field (name "PART NUMBER") "R0402_1K_1%_0.0625W_100PPM")
        (field (name "POWER") "0.0625W")
        (field (name "AUTHOR") "CERN DEM JLC")
      )
      (libsource (lib "Resistors") (part "Resistor - 1%"))
    )
    (comp (ref "R78")
      (value "300")
      (footprint "RESC1005X40N")
      (description "Resistor - 1%")
      (fields
        (field (name "PART NUMBER") "R0402_300R_1%_0.0625W_100PPM")
        (field (name "POWER") "0.0625W")
        (field (name "AUTHOR") "CERN DEM JLC")
      )
      (libsource (lib "Resistors") (part "Resistor - 1%"))
    )
    (comp (ref "R81")
      (value "1k")
      (footprint "RESC1005X40N")
      (description "Resistor - 1%")
      (fields
        (field (name "PART NUMBER") "R0402_1K_1%_0.0625W_100PPM")
        (field (name "POWER") "0.0625W")
        (field (name "AUTHOR") "CERN DEM JLC")
      )
      (libsource (lib "Resistors") (part "Resistor - 1%"))
    )
    (comp (ref "R82")
      (value "1k")
      (footprint "RESC1005X40N")
      (description "Resistor - 1%")
      (fields
        (field (name "PART NUMBER") "R0402_1K_1%_0.0625W_100PPM")
        (field (name "POWER") "0.0625W")
        (field (name "AUTHOR") "CERN DEM JLC")
      )
      (libsource (lib "Resistors") (part "Resistor - 1%"))
    )
    (comp (ref "R83")
      (value "0")
      (footprint "RESC0603X28N")
      (description "Resistor")
      (fields
        (field (name "PART NUMBER") "R0201_0R_JUMPER")
        (field (name "MANUFACTURER") "GENERIC")
        (field (name "AUTHOR") "CERN DEM JLC")
      )
      (libsource (lib "Resistors") (part "Resistor"))
    )
    (comp (ref "R84")
      (value "0")
      (footprint "RESC0603X28N")
      (description "Resistor")
      (fields
        (field (name "PART NUMBER") "R0201_0R_JUMPER")
        (field (name "MANUFACTURER") "GENERIC")
        (field (name "AUTHOR") "CERN DEM JLC")
      )
      (libsource (lib "Resistors") (part "Resistor"))
    )
    (comp (ref "T16")
      (value "BSH103")
      (footprint "SOT95P230X110-3N")
      (description "N-CHANNEL MOSFET WITH DIODE")
      (fields (field (name "MANUFACTURER") "NEXPERIA") (field (name "AUTHOR") "CERN DEM JLC"))
      (libsource (lib "ICs And Semiconductors") (part "N-MOSFET-D 1G 2S 3D"))
    )
  )
  (nets
    (net (code "2") (name "/CFG_CCLK") (class "Default")
      (node (ref "IC4") (pin "L12") (pinfunction "CCLK_0_L12") (pintype "bidirectional"))
    )
    (net (code "3") (name "/DXN_0") (class "Default")
      (node (ref "IC4") (pin "N9") (pinfunction "DXN_0_N9") (pintype "input"))
      (node (ref "R84") (pin "2") (pinfunction "2_2") (pintype "passive"))
    )
    (net (code "4") (name "/DXP_0") (class "Default")
      (node (ref "IC4") (pin "N10") (pinfunction "DXP_0_N10") (pintype "input"))
      (node (ref "R83") (pin "2") (pinfunction "2_2") (pintype "passive"))
    )
    (net (code "5") (name "/FPGA_DONE") (class "Default")
      (node (ref "IC4") (pin "G11") (pinfunction "DONE_0_G11") (pintype "bidirectional"))
      (node (ref "R78") (pin "1") (pinfunction "1_1") (pintype "passive"))
      (node (ref "T16") (pin "1") (pinfunction "G_1") (pintype "passive"))
    )
    (net (code "6") (name "/FPGA_INIT_B") (class "Default")
      (node (ref "IC4") (pin "U12") (pinfunction "INIT_B_0_U12") (pintype "bidirectional"))
      (node (ref "R81") (pin "1") (pinfunction "1_1") (pintype "passive"))
    )
    (net (code "7") (name "/FPGA_JTAG.TCK") (class "Default")
      (node (ref "IC4") (pin "V12") (pinfunction "TCK_0_V12") (pintype "input"))
    )
    (net (code "8") (name "/FPGA_JTAG.TDI") (class "Default")
      (node (ref "IC4") (pin "R13") (pinfunction "TDI_0_R13") (pintype "input"))
    )
    (net (code "9") (name "/FPGA_JTAG.TDO") (class "Default")
      (node (ref "IC4") (pin "U13") (pinfunction "TDO_0_U13") (pintype "output"))
    )
    (net (code "10") (name "/FPGA_JTAG.TMS") (class "Default")
      (node (ref "IC4") (pin "T13") (pinfunction "TMS_0_T13") (pintype "input"))
    )
    (net (code "12") (name "/PROGRAM_B") (class "Default")
      (node (ref "IC4") (pin "N12") (pinfunction "PROGRAM_B_0_N12") (pintype "input"))
      (node (ref "R82") (pin "1") (pinfunction "1_1") (pintype "passive"))
    )
    (net (code "13") (name "/XADC_GND") (class "Default")
      (node (ref "C97") (pin "1") (pinfunction "1_1") (pintype "passive"))
      (node (ref "C98") (pin "1") (pinfunction "1_1") (pintype "passive"))
      (node (ref "IC4") (pin "K9") (pinfunction "GNDADC_0_K9") (pintype "power_in"))
      (node (ref "IC4") (pin "L10") (pinfunction "VP_0_L10") (pintype "input"))
      (node (ref "IC4") (pin "L9") (pinfunction "VREFN_0_L9") (pintype "input"))
      (node (ref "IC4") (pin "M10") (pinfunction "VREFP_0_M10") (pintype "input"))
      (node (ref "IC4") (pin "M9") (pinfunction "VN_0_M9") (pintype "input"))
      (node (ref "L4") (pin "2") (pinfunction "2_2") (pintype "passive"))
    )
    (net (code "14") (name "/XADC_VCC") (class "Default")
      (node (ref "C97") (pin "2") (pinfunction "2_2") (pintype "passive"))
      (node (ref "C98") (pin "2") (pinfunction "2_2") (pintype "passive"))
      (node (ref "IC4") (pin "K10") (pinfunction "VCCADC_0_K10") (pintype "power_in"))
      (node (ref "L3") (pin "2") (pinfunction "2_2") (pintype "passive"))
    )
    (net (code "15") (name "GND") (class "Default")
      (node (ref "C100") (pin "1") (pinfunction "1_1") (pintype "passive"))
      (node (ref "C101") (pin "1") (pinfunction "1_1") (pintype "passive"))
      (node (ref "C102") (pin "1") (pinfunction "1_1") (pintype "passive"))
      (node (ref "C103") (pin "2") (pinfunction "2_2") (pintype "passive"))
      (node (ref "C104") (pin "1") (pinfunction "1_1") (pintype "passive"))
      (node (ref "C105") (pin "1") (pinfunction "1_1") (pintype "passive"))
      (node (ref "C106") (pin "1") (pinfunction "1_1") (pintype "passive"))
      (node (ref "C107") (pin "1") (pinfunction "1_1") (pintype "passive"))
      (node (ref "C108") (pin "1") (pinfunction "1_1") (pintype "passive"))
      (node (ref "C109") (pin "1") (pinfunction "1_1") (pintype "passive"))
      (node (ref "C110") (pin "1") (pinfunction "1_1") (pintype "passive"))
      (node (ref "C112") (pin "1") (pinfunction "1_1") (pintype "passive"))
      (node (ref "C113") (pin "1") (pinfunction "1_1") (pintype "passive"))
      (node (ref "C115") (pin "1") (pinfunction "1_1") (pintype "passive"))
      (node (ref "C116") (pin "1") (pinfunction "1_1") (pintype "passive"))
      (node (ref "C117") (pin "1") (pinfunction "1_1") (pintype "passive"))
      (node (ref "C118") (pin "1") (pinfunction "1_1") (pintype "passive"))
      (node (ref "C119") (pin "1") (pinfunction "1_1") (pintype "passive"))
      (node (ref "C120") (pin "1") (pinfunction "1_1") (pintype "passive"))
      (node (ref "C121") (pin "1") (pinfunction "1_1") (pintype "passive"))
      (node (ref "C122") (pin "1") (pinfunction "1_1") (pintype "passive"))
      (node (ref "C123") (pin "1") (pinfunction "1_1") (pintype "passive"))
      (node (ref "C124") (pin "1") (pinfunction "1_1") (pintype "passive"))
      (node (ref "C125") (pin "1") (pinfunction "1_1") (pintype "passive"))
      (node (ref "C126") (pin "1") (pinfunction "1_1") (pintype "passive"))
      (node (ref "C127") (pin "1") (pinfunction "1_1") (pintype "passive"))
      (node (ref "C128") (pin "1") (pinfunction "1_1") (pintype "passive"))
      (node (ref "C129") (pin "1") (pinfunction "1_1") (pintype "passive"))
      (node (ref "C130") (pin "1") (pinfunction "1_1") (pintype "passive"))
      (node (ref "C131") (pin "1") (pinfunction "1_1") (pintype "passive"))
      (node (ref "C132") (pin "1") (pinfunction "1_1") (pintype "passive"))
      (node (ref "C133") (pin "1") (pinfunction "1_1") (pintype "passive"))
      (node (ref "C134") (pin "1") (pinfunction "1_1") (pintype "passive"))
      (node (ref "C135") (pin "1") (pinfunction "1_1") (pintype "passive"))
      (node (ref "C136") (pin "1") (pinfunction "1_1") (pintype "passive"))
      (node (ref "C137") (pin "1") (pinfunction "1_1") (pintype "passive"))
      (node (ref "C138") (pin "1") (pinfunction "1_1") (pintype "passive"))
      (node (ref "C139") (pin "1") (pinfunction "1_1") (pintype "passive"))
      (node (ref "C140") (pin "1") (pinfunction "1_1") (pintype "passive"))
      (node (ref "C141") (pin "1") (pinfunction "1_1") (pintype "passive"))
      (node (ref "C142") (pin "1") (pinfunction "1_1") (pintype "passive"))
      (node (ref "C143") (pin "1") (pinfunction "1_1") (pintype "passive"))
      (node (ref "C144") (pin "1") (pinfunction "1_1") (pintype "passive"))
      (node (ref "C145") (pin "1") (pinfunction "1_1") (pintype "passive"))
      (node (ref "C146") (pin "1") (pinfunction "1_1") (pintype "passive"))
      (node (ref "C147") (pin "1") (pinfunction "1_1") (pintype "passive"))
      (node (ref "C148") (pin "1") (pinfunction "1_1") (pintype "passive"))
      (node (ref "C149") (pin "1") (pinfunction "1_1") (pintype "passive"))
      (node (ref "C150") (pin "1") (pinfunction "1_1") (pintype "passive"))
      (node (ref "C151") (pin "1") (pinfunction "1_1") (pintype "passive"))
      (node (ref "C152") (pin "1") (pinfunction "1_1") (pintype "passive"))
      (node (ref "C153") (pin "1") (pinfunction "1_1") (pintype "passive"))
      (node (ref "C156") (pin "1") (pinfunction "1_1") (pintype "passive"))
      (node (ref "C157") (pin "1") (pinfunction "1_1") (pintype "passive"))
      (node (ref "C158") (pin "1") (pinfunction "1_1") (pintype "passive"))
      (node (ref "C159") (pin "1") (pinfunction "1_1") (pintype "passive"))
      (node (ref "C160") (pin "1") (pinfunction "1_1") (pintype "passive"))
      (node (ref "C161") (pin "1") (pinfunction "1_1") (pintype "passive"))
      (node (ref "C162") (pin "1") (pinfunction "1_1") (pintype "passive"))
      (node (ref "C163") (pin "1") (pinfunction "1_1") (pintype "passive"))
      (node (ref "C164") (pin "1") (pinfunction "1_1") (pintype "passive"))
      (node (ref "C168") (pin "1") (pinfunction "1_1") (pintype "passive"))
      (node (ref "C169") (pin "1") (pinfunction "1_1") (pintype "passive"))
      (node (ref "C170") (pin "1") (pinfunction "1_1") (pintype "passive"))
      (node (ref "C172") (pin "1") (pinfunction "1_1") (pintype "passive"))
      (node (ref "C173") (pin "1") (pinfunction "1_1") (pintype "passive"))
      (node (ref "C174") (pin "1") (pinfunction "1_1") (pintype "passive"))
      (node (ref "C175") (pin "1") (pinfunction "1_1") (pintype "passive"))
      (node (ref "C177") (pin "1") (pinfunction "1_1") (pintype "passive"))
      (node (ref "C178") (pin "1") (pinfunction "1_1") (pintype "passive"))
      (node (ref "C182") (pin "1") (pinfunction "1_1") (pintype "passive"))
      (node (ref "C183") (pin "1") (pinfunction "1_1") (pintype "passive"))
      (node (ref "C288") (pin "1") (pinfunction "1_1") (pintype "passive"))
      (node (ref "C289") (pin "1") (pinfunction "1_1") (pintype "passive"))
      (node (ref "C308") (pin "1") (pinfunction "1_1") (pintype "passive"))
      (node (ref "C309") (pin "1") (pinfunction "1_1") (pintype "passive"))
      (node (ref "C310") (pin "1") (pinfunction "1_1") (pintype "passive"))
      (node (ref "C311") (pin "1") (pinfunction "1_1") (pintype "passive"))
      (node (ref "C312") (pin "1") (pinfunction "1_1") (pintype "passive"))
      (node (ref "C313") (pin "1") (pinfunction "1_1") (pintype "passive"))
      (node (ref "C314") (pin "1") (pinfunction "1_1") (pintype "passive"))
      (node (ref "C315") (pin "1") (pinfunction "1_1") (pintype "passive"))
      (node (ref "C316") (pin "1") (pinfunction "1_1") (pintype "passive"))
      (node (ref "C317") (pin "1") (pinfunction "1_1") (pintype "passive"))
      (node (ref "C318") (pin "1") (pinfunction "1_1") (pintype "passive"))
      (node (ref "C319") (pin "1") (pinfunction "1_1") (pintype "passive"))
      (node (ref "C320") (pin "1") (pinfunction "1_1") (pintype "passive"))
      (node (ref "C99") (pin "1") (pinfunction "1_1") (pintype "passive"))
      (node (ref "IC4") (pin "A11") (pinfunction "GND_A11") (pintype "power_in"))
      (node (ref "IC4") (pin "A12") (pinfunction "GND_A12") (pintype "power_in"))
      (node (ref "IC4") (pin "A2") (pinfunction "GND_A2") (pintype "power_in"))
      (node (ref "IC4") (pin "A22") (pinfunction "GND_A22") (pintype "power_in"))
      (node (ref "IC4") (pin "A3") (pinfunction "GND_A3") (pintype "power_in"))
      (node (ref "IC4") (pin "A5") (pinfunction "GND_A5") (pintype "power_in"))
      (node (ref "IC4") (pin "A7") (pinfunction "GND_A7") (pintype "power_in"))
      (node (ref "IC4") (pin "A9") (pinfunction "GND_A9") (pintype "power_in"))
      (node (ref "IC4") (pin "AA12") (pinfunction "GND_AA12") (pintype "power_in"))
      (node (ref "IC4") (pin "AA2") (pinfunction "GND_AA2") (pintype "power_in"))
      (node (ref "IC4") (pin "AA22") (pinfunction "GND_AA22") (pintype "power_in"))
      (node (ref "IC4") (pin "AB19") (pinfunction "GND_AB19") (pintype "power_in"))
      (node (ref "IC4") (pin "AB9") (pinfunction "GND_AB9") (pintype "power_in"))
      (node (ref "IC4") (pin "B12") (pinfunction "GND_B12") (pintype "power_in"))
      (node (ref "IC4") (pin "B19") (pinfunction "GND_B19") (pintype "power_in"))
      (node (ref "IC4") (pin "B3") (pinfunction "GND_B3") (pintype "power_in"))
      (node (ref "IC4") (pin "C10") (pinfunction "GND_C10") (pintype "power_in"))
      (node (ref "IC4") (pin "C12") (pinfunction "GND_C12") (pintype "power_in"))
      (node (ref "IC4") (pin "C16") (pinfunction "GND_C16") (pintype "power_in"))
      (node (ref "IC4") (pin "C3") (pinfunction "GND_C3") (pintype "power_in"))
      (node (ref "IC4") (pin "C6") (pinfunction "GND_C6") (pintype "power_in"))
      (node (ref "IC4") (pin "D12") (pinfunction "GND_D12") (pintype "power_in"))
      (node (ref "IC4") (pin "D13") (pinfunction "GND_D13") (pintype "power_in"))
      (node (ref "IC4") (pin "D3") (pinfunction "GND_D3") (pintype "power_in"))
      (node (ref "IC4") (pin "D4") (pinfunction "GND_D4") (pintype "power_in"))
      (node (ref "IC4") (pin "D8") (pinfunction "GND_D8") (pintype "power_in"))
      (node (ref "IC4") (pin "E11") (pinfunction "GND_E11") (pintype "power_in"))
      (node (ref "IC4") (pin "E12") (pinfunction "VCCBATT_0_E12") (pintype "power_in"))
      (node (ref "IC4") (pin "E20") (pinfunction "GND_E20") (pintype "power_in"))
      (node (ref "IC4") (pin "E4") (pinfunction "GND_E4") (pintype "power_in"))
      (node (ref "IC4") (pin "E5") (pinfunction "GND_E5") (pintype "power_in"))
      (node (ref "IC4") (pin "E7") (pinfunction "GND_E7") (pintype "power_in"))
      (node (ref "IC4") (pin "E9") (pinfunction "GND_E9") (pintype "power_in"))
      (node (ref "IC4") (pin "F11") (pinfunction "GND_F11") (pintype "power_in"))
      (node (ref "IC4") (pin "F17") (pinfunction "GND_F17") (pintype "power_in"))
      (node (ref "IC4") (pin "F5") (pinfunction "GND_F5") (pintype "power_in"))
      (node (ref "IC4") (pin "G10") (pinfunction "GND_G10") (pintype "power_in"))
      (node (ref "IC4") (pin "G12") (pinfunction "GND_G12") (pintype "power_in"))
      (node (ref "IC4") (pin "G14") (pinfunction "GND_G14") (pintype "power_in"))
      (node (ref "IC4") (pin "G5") (pinfunction "GND_G5") (pintype "power_in"))
      (node (ref "IC4") (pin "G6") (pinfunction "GND_G6") (pintype "power_in"))
      (node (ref "IC4") (pin "G7") (pinfunction "GND_G7") (pintype "power_in"))
      (node (ref "IC4") (pin "G8") (pinfunction "GND_G8") (pintype "power_in"))
      (node (ref "IC4") (pin "G9") (pinfunction "GND_G9") (pintype "power_in"))
      (node (ref "IC4") (pin "H1") (pinfunction "GND_H1") (pintype "power_in"))
      (node (ref "IC4") (pin "H11") (pinfunction "GND_H11") (pintype "power_in"))
      (node (ref "IC4") (pin "H21") (pinfunction "GND_H21") (pintype "power_in"))
      (node (ref "IC4") (pin "H7") (pinfunction "GND_H7") (pintype "power_in"))
      (node (ref "IC4") (pin "H9") (pinfunction "GND_H9") (pintype "power_in"))
      (node (ref "IC4") (pin "J10") (pinfunction "GND_J10") (pintype "power_in"))
      (node (ref "IC4") (pin "J12") (pinfunction "GND_J12") (pintype "power_in"))
      (node (ref "IC4") (pin "J18") (pinfunction "GND_J18") (pintype "power_in"))
      (node (ref "IC4") (pin "J8") (pinfunction "GND_J8") (pintype "power_in"))
      (node (ref "IC4") (pin "K11") (pinfunction "GND_K11") (pintype "power_in"))
      (node (ref "IC4") (pin "K15") (pinfunction "GND_K15") (pintype "power_in"))
      (node (ref "IC4") (pin "K5") (pinfunction "GND_K5") (pintype "power_in"))
      (node (ref "IC4") (pin "K7") (pinfunction "GND_K7") (pintype "power_in"))
      (node (ref "IC4") (pin "L2") (pinfunction "GND_L2") (pintype "power_in"))
      (node (ref "IC4") (pin "L22") (pinfunction "GND_L22") (pintype "power_in"))
      (node (ref "IC4") (pin "L8") (pinfunction "GND_L8") (pintype "power_in"))
      (node (ref "IC4") (pin "M11") (pinfunction "GND_M11") (pintype "power_in"))
      (node (ref "IC4") (pin "M19") (pinfunction "GND_M19") (pintype "power_in"))
      (node (ref "IC4") (pin "M7") (pinfunction "GND_M7") (pintype "power_in"))
      (node (ref "IC4") (pin "N16") (pinfunction "GND_N16") (pintype "power_in"))
      (node (ref "IC4") (pin "N6") (pinfunction "GND_N6") (pintype "power_in"))
      (node (ref "IC4") (pin "N8") (pinfunction "GND_N8") (pintype "power_in"))
      (node (ref "IC4") (pin "P11") (pinfunction "GND_P11") (pintype "power_in"))
      (node (ref "IC4") (pin "P13") (pinfunction "GND_P13") (pintype "power_in"))
      (node (ref "IC4") (pin "P3") (pinfunction "GND_P3") (pintype "power_in"))
      (node (ref "IC4") (pin "P7") (pinfunction "GND_P7") (pintype "power_in"))
      (node (ref "IC4") (pin "P9") (pinfunction "GND_P9") (pintype "power_in"))
      (node (ref "IC4") (pin "R10") (pinfunction "GND_R10") (pintype "power_in"))
      (node (ref "IC4") (pin "R12") (pinfunction "GND_R12") (pintype "power_in"))
      (node (ref "IC4") (pin "R20") (pinfunction "GND_R20") (pintype "power_in"))
      (node (ref "IC4") (pin "R8") (pinfunction "GND_R8") (pintype "power_in"))
      (node (ref "IC4") (pin "T11") (pinfunction "GND_T11") (pintype "power_in"))
      (node (ref "IC4") (pin "T17") (pinfunction "GND_T17") (pintype "power_in"))
      (node (ref "IC4") (pin "T7") (pinfunction "GND_T7") (pintype "power_in"))
      (node (ref "IC4") (pin "T9") (pinfunction "GND_T9") (pintype "power_in"))
      (node (ref "IC4") (pin "U10") (pinfunction "M1_0_U10") (pintype "input"))
      (node (ref "IC4") (pin "U14") (pinfunction "GND_U14") (pintype "power_in"))
      (node (ref "IC4") (pin "U4") (pinfunction "GND_U4") (pintype "power_in"))
      (node (ref "IC4") (pin "U9") (pinfunction "M2_0_U9") (pintype "input"))
      (node (ref "IC4") (pin "V1") (pinfunction "GND_V1") (pintype "power_in"))
      (node (ref "IC4") (pin "V11") (pinfunction "GND_V11") (pintype "power_in"))
      (node (ref "IC4") (pin "V21") (pinfunction "GND_V21") (pintype "power_in"))
      (node (ref "IC4") (pin "W18") (pinfunction "GND_W18") (pintype "power_in"))
      (node (ref "IC4") (pin "W8") (pinfunction "GND_W8") (pintype "power_in"))
      (node (ref "IC4") (pin "Y15") (pinfunction "GND_Y15") (pintype "power_in"))
      (node (ref "IC4") (pin "Y5") (pinfunction "GND_Y5") (pintype "power_in"))
      (node (ref "L4") (pin "1") (pinfunction "1_1") (pintype "passive"))
      (node (ref "R83") (pin "1") (pinfunction "1_1") (pintype "passive"))
      (node (ref "R84") (pin "1") (pinfunction "1_1") (pintype "passive"))
      (node (ref "T16") (pin "2") (pinfunction "S_2") (pintype "passive"))
    )
    (net (code "16") (name "MGTAVCC") (class "Default")
      (node (ref "C170") (pin "2") (pinfunction "2_2") (pintype "passive"))
      (node (ref "C172") (pin "2") (pinfunction "2_2") (pintype "passive"))
      (node (ref "C99") (pin "2") (pinfunction "2_2") (pintype "passive"))
      (node (ref "IC4") (pin "D10") (pinfunction "MGTAVCC_D10") (pintype "power_in"))
      (node (ref "IC4") (pin "D6") (pinfunction "MGTAVCC_D6") (pintype "power_in"))
      (node (ref "IC4") (pin "E8") (pinfunction "MGTAVCC_E8") (pintype "power_in"))
      (node (ref "IC4") (pin "F7") (pinfunction "MGTAVCC_F7") (pintype "power_in"))
      (node (ref "IC4") (pin "F9") (pinfunction "MGTAVCC_F9") (pintype "power_in"))
    )
    (net (code "17") (name "MGTAVTT") (class "Default")
      (node (ref "C156") (pin "2") (pinfunction "2_2") (pintype "passive"))
      (node (ref "C168") (pin "2") (pinfunction "2_2") (pintype "passive"))
      (node (ref "C169") (pin "2") (pinfunction "2_2") (pintype "passive"))
      (node (ref "IC4") (pin "B11") (pinfunction "MGTAVTT_B11") (pintype "power_in"))
      (node (ref "IC4") (pin "B5") (pinfunction "MGTAVTT_B5") (pintype "power_in"))
      (node (ref "IC4") (pin "B7") (pinfunction "MGTAVTT_B7") (pintype "power_in"))
      (node (ref "IC4") (pin "B9") (pinfunction "MGTAVTT_B9") (pintype "power_in"))
      (node (ref "IC4") (pin "C4") (pinfunction "MGTAVTT_C4") (pintype "power_in"))
      (node (ref "IC4") (pin "C8") (pinfunction "MGTAVTT_C8") (pintype "power_in"))
    )
    (net (code "18") (name "Net-(LD1-A)") (class "Default")
      (node (ref "LD1") (pin "2") (pinfunction "A_2") (pintype "passive"))
      (node (ref "R76") (pin "1") (pinfunction "1_1") (pintype "passive"))
    )
    (net (code "19") (name "Net-(LD1-C)") (class "Default")
      (node (ref "LD1") (pin "1") (pinfunction "C_1") (pintype "passive"))
      (node (ref "T16") (pin "3") (pinfunction "D_3") (pintype "passive"))
    )
    (net (code "20") (name "P1V0") (class "Default")
      (node (ref "C103") (pin "1") (pinfunction "1_1") (pintype "passive"))
      (node (ref "C104") (pin "2") (pinfunction "2_2") (pintype "passive"))
      (node (ref "C105") (pin "2") (pinfunction "2_2") (pintype "passive"))
      (node (ref "C106") (pin "2") (pinfunction "2_2") (pintype "passive"))
      (node (ref "C107") (pin "2") (pinfunction "2_2") (pintype "passive"))
      (node (ref "C108") (pin "2") (pinfunction "2_2") (pintype "passive"))
      (node (ref "C109") (pin "2") (pinfunction "2_2") (pintype "passive"))
      (node (ref "C145") (pin "2") (pinfunction "2_2") (pintype "passive"))
      (node (ref "C146") (pin "2") (pinfunction "2_2") (pintype "passive"))
      (node (ref "C147") (pin "2") (pinfunction "2_2") (pintype "passive"))
      (node (ref "C148") (pin "2") (pinfunction "2_2") (pintype "passive"))
      (node (ref "C149") (pin "2") (pinfunction "2_2") (pintype "passive"))
      (node (ref "C150") (pin "2") (pinfunction "2_2") (pintype "passive"))
      (node (ref "C151") (pin "2") (pinfunction "2_2") (pintype "passive"))
      (node (ref "C152") (pin "2") (pinfunction "2_2") (pintype "passive"))
      (node (ref "C308") (pin "2") (pinfunction "2_2") (pintype "passive"))
      (node (ref "C309") (pin "2") (pinfunction "2_2") (pintype "passive"))
      (node (ref "C310") (pin "2") (pinfunction "2_2") (pintype "passive"))
      (node (ref "C311") (pin "2") (pinfunction "2_2") (pintype "passive"))
      (node (ref "C312") (pin "2") (pinfunction "2_2") (pintype "passive"))
      (node (ref "C313") (pin "2") (pinfunction "2_2") (pintype "passive"))
      (node (ref "C314") (pin "2") (pinfunction "2_2") (pintype "passive"))
      (node (ref "C315") (pin "2") (pinfunction "2_2") (pintype "passive"))
      (node (ref "C316") (pin "2") (pinfunction "2_2") (pintype "passive"))
      (node (ref "C317") (pin "2") (pinfunction "2_2") (pintype "passive"))
      (node (ref "C318") (pin "2") (pinfunction "2_2") (pintype "passive"))
      (node (ref "C319") (pin "2") (pinfunction "2_2") (pintype "passive"))
      (node (ref "IC4") (pin "H10") (pinfunction "VCCINT_H10") (pintype "power_in"))
      (node (ref "IC4") (pin "H8") (pinfunction "VCCINT_H8") (pintype "power_in"))
      (node (ref "IC4") (pin "J7") (pinfunction "VCCINT_J7") (pintype "power_in"))
      (node (ref "IC4") (pin "J9") (pinfunction "VCCINT_J9") (pintype "power_in"))
      (node (ref "IC4") (pin "K8") (pinfunction "VCCINT_K8") (pintype "power_in"))
      (node (ref "IC4") (pin "L7") (pinfunction "VCCINT_L7") (pintype "power_in"))
      (node (ref "IC4") (pin "M8") (pinfunction "VCCINT_M8") (pintype "power_in"))
      (node (ref "IC4") (pin "N7") (pinfunction "VCCINT_N7") (pintype "power_in"))
      (node (ref "IC4") (pin "P10") (pinfunction "VCCINT_P10") (pintype "power_in"))
      (node (ref "IC4") (pin "P8") (pinfunction "VCCINT_P8") (pintype "power_in"))
      (node (ref "IC4") (pin "R7") (pinfunction "VCCINT_R7") (pintype "power_in"))
      (node (ref "IC4") (pin "R9") (pinfunction "VCCINT_R9") (pintype "power_in"))
      (node (ref "IC4") (pin "T10") (pinfunction "VCCINT_T10") (pintype "power_in"))
      (node (ref "IC4") (pin "T8") (pinfunction "VCCINT_T8") (pintype "power_in"))
    )
    (net (code "21") (name "P1V5") (class "Default")
      (node (ref "C101") (pin "2") (pinfunction "2_2") (pintype "passive"))
      (node (ref "C135") (pin "2") (pinfunction "2_2") (pintype "passive"))
      (node (ref "C136") (pin "2") (pinfunction "2_2") (pintype "passive"))
      (node (ref "C137") (pin "2") (pinfunction "2_2") (pintype "passive"))
      (node (ref "C138") (pin "2") (pinfunction "2_2") (pintype "passive"))
      (node (ref "C139") (pin "2") (pinfunction "2_2") (pintype "passive"))
      (node (ref "C140") (pin "2") (pinfunction "2_2") (pintype "passive"))
      (node (ref "IC4") (pin "G19") (pinfunction "VCCO_15_G19") (pintype "power_in"))
      (node (ref "IC4") (pin "H16") (pinfunction "VCCO_15_H16") (pintype "power_in"))
      (node (ref "IC4") (pin "J13") (pinfunction "VCCO_15_J13") (pintype "power_in"))
      (node (ref "IC4") (pin "K20") (pinfunction "VCCO_15_K20") (pintype "power_in"))
      (node (ref "IC4") (pin "L17") (pinfunction "VCCO_15_L17") (pintype "power_in"))
      (node (ref "IC4") (pin "N21") (pinfunction "VCCO_15_N21") (pintype "power_in"))
    )
    (net (code "22") (name "P1V8") (class "Default")
      (node (ref "C173") (pin "2") (pinfunction "2_2") (pintype "passive"))
      (node (ref "L3") (pin "1") (pinfunction "1_1") (pintype "passive"))
      (node (ref "L5") (pin "1") (pinfunction "1_1") (pintype "passive"))
    )
    (net (code "23") (name "P2V5") (class "Default")
      (node (ref "C102") (pin "2") (pinfunction "2_2") (pintype "passive"))
      (node (ref "C153") (pin "2") (pinfunction "2_2") (pintype "passive"))
      (node (ref "C175") (pin "2") (pinfunction "2_2") (pintype "passive"))
      (node (ref "C177") (pin "2") (pinfunction "2_2") (pintype "passive"))
      (node (ref "C178") (pin "2") (pinfunction "2_2") (pintype "passive"))
      (node (ref "C182") (pin "2") (pinfunction "2_2") (pintype "passive"))
      (node (ref "C183") (pin "2") (pinfunction "2_2") (pintype "passive"))
      (node (ref "C288") (pin "2") (pinfunction "2_2") (pintype "passive"))
      (node (ref "C289") (pin "2") (pinfunction "2_2") (pintype "passive"))
      (node (ref "IC4") (pin "F12") (pinfunction "VCCO_0_F12") (pintype "power_in"))
      (node (ref "IC4") (pin "M14") (pinfunction "VCCO_14_M14") (pintype "power_in"))
      (node (ref "IC4") (pin "P18") (pinfunction "VCCO_14_P18") (pintype "power_in"))
      (node (ref "IC4") (pin "R15") (pinfunction "VCCO_14_R15") (pintype "power_in"))
      (node (ref "IC4") (pin "T12") (pinfunction "VCCO_0_T12") (pintype "power_in"))
      (node (ref "IC4") (pin "T22") (pinfunction "VCCO_14_T22") (pintype "power_in"))
      (node (ref "IC4") (pin "U11") (pinfunction "M0_0_U11") (pintype "input"))
      (node (ref "IC4") (pin "U19") (pinfunction "VCCO_14_U19") (pintype "power_in"))
      (node (ref "IC4") (pin "U8") (pinfunction "CFGBVS_0_U8") (pintype "input"))
      (node (ref "IC4") (pin "Y20") (pinfunction "VCCO_14_Y20") (pintype "power_in"))
      (node (ref "R78") (pin "2") (pinfunction "2_2") (pintype "passive"))
      (node (ref "R81") (pin "2") (pinfunction "2_2") (pintype "passive"))
      (node (ref "R82") (pin "2") (pinfunction "2_2") (pintype "passive"))
    )
    (net (code "24") (name "P3V3") (class "Default")
      (node (ref "R76") (pin "2") (pinfunction "2_2") (pintype "passive"))
    )
    (net (code "25") (name "VADJ_FMC") (class "Default")
      (node (ref "C100") (pin "2") (pinfunction "2_2") (pintype "passive"))
      (node (ref "C115") (pin "2") (pinfunction "2_2") (pintype "passive"))
      (node (ref "C116") (pin "2") (pinfunction "2_2") (pintype "passive"))
      (node (ref "C117") (pin "2") (pinfunction "2_2") (pintype "passive"))
      (node (ref "C118") (pin "2") (pinfunction "2_2") (pintype "passive"))
      (node (ref "C119") (pin "2") (pinfunction "2_2") (pintype "passive"))
      (node (ref "C120") (pin "2") (pinfunction "2_2") (pintype "passive"))
      (node (ref "C121") (pin "2") (pinfunction "2_2") (pintype "passive"))
      (node (ref "C122") (pin "2") (pinfunction "2_2") (pintype "passive"))
      (node (ref "C123") (pin "2") (pinfunction "2_2") (pintype "passive"))
      (node (ref "C124") (pin "2") (pinfunction "2_2") (pintype "passive"))
      (node (ref "C125") (pin "2") (pinfunction "2_2") (pintype "passive"))
      (node (ref "C126") (pin "2") (pinfunction "2_2") (pintype "passive"))
      (node (ref "C127") (pin "2") (pinfunction "2_2") (pintype "passive"))
      (node (ref "C128") (pin "2") (pinfunction "2_2") (pintype "passive"))
      (node (ref "C129") (pin "2") (pinfunction "2_2") (pintype "passive"))
      (node (ref "C130") (pin "2") (pinfunction "2_2") (pintype "passive"))
      (node (ref "C131") (pin "2") (pinfunction "2_2") (pintype "passive"))
      (node (ref "C132") (pin "2") (pinfunction "2_2") (pintype "passive"))
      (node (ref "C133") (pin "2") (pinfunction "2_2") (pintype "passive"))
      (node (ref "C134") (pin "2") (pinfunction "2_2") (pintype "passive"))
      (node (ref "C141") (pin "2") (pinfunction "2_2") (pintype "passive"))
      (node (ref "C142") (pin "2") (pinfunction "2_2") (pintype "passive"))
      (node (ref "C143") (pin "2") (pinfunction "2_2") (pintype "passive"))
      (node (ref "C144") (pin "2") (pinfunction "2_2") (pintype "passive"))
      (node (ref "IC4") (pin "A17") (pinfunction "VCCO_16_A17") (pintype "power_in"))
      (node (ref "IC4") (pin "AA17") (pinfunction "VCCO_13_AA17") (pintype "power_in"))
      (node (ref "IC4") (pin "AA7") (pinfunction "VCCO_34_AA7") (pintype "power_in"))
      (node (ref "IC4") (pin "AB14") (pinfunction "VCCO_13_AB14") (pintype "power_in"))
      (node (ref "IC4") (pin "AB4") (pinfunction "VCCO_34_AB4") (pintype "power_in"))
      (node (ref "IC4") (pin "B14") (pinfunction "VCCO_16_B14") (pintype "power_in"))
      (node (ref "IC4") (pin "C1") (pinfunction "VCCO_35_C1") (pintype "power_in"))
      (node (ref "IC4") (pin "C21") (pinfunction "VCCO_16_C21") (pintype "power_in"))
      (node (ref "IC4") (pin "D18") (pinfunction "VCCO_16_D18") (pintype "power_in"))
      (node (ref "IC4") (pin "E15") (pinfunction "VCCO_16_E15") (pintype "power_in"))
      (node (ref "IC4") (pin "F2") (pinfunction "VCCO_35_F2") (pintype "power_in"))
      (node (ref "IC4") (pin "F22") (pinfunction "VCCO_16_F22") (pintype "power_in"))
      (node (ref "IC4") (pin "H6") (pinfunction "VCCO_35_H6") (pintype "power_in"))
      (node (ref "IC4") (pin "J3") (pinfunction "VCCO_35_J3") (pintype "power_in"))
      (node (ref "IC4") (pin "M4") (pinfunction "VCCO_35_M4") (pintype "power_in"))
      (node (ref "IC4") (pin "N1") (pinfunction "VCCO_35_N1") (pintype "power_in"))
      (node (ref "IC4") (pin "R5") (pinfunction "VCCO_34_R5") (pintype "power_in"))
      (node (ref "IC4") (pin "T2") (pinfunction "VCCO_34_T2") (pintype "power_in"))
      (node (ref "IC4") (pin "V16") (pinfunction "VCCO_13_V16") (pintype "power_in"))
      (node (ref "IC4") (pin "V6") (pinfunction "VCCO_34_V6") (pintype "power_in"))
      (node (ref "IC4") (pin "W13") (pinfunction "VCCO_13_W13") (pintype "power_in"))
      (node (ref "IC4") (pin "W3") (pinfunction "VCCO_34_W3") (pintype "power_in"))
      (node (ref "IC4") (pin "Y10") (pinfunction "VCCO_13_Y10") (pintype "power_in"))
    )
    (net (code "26") (name "VCCAUX") (class "Default")
      (node (ref "C157") (pin "2") (pinfunction "2_2") (pintype "passive"))
      (node (ref "C158") (pin "2") (pinfunction "2_2") (pintype "passive"))
      (node (ref "C159") (pin "2") (pinfunction "2_2") (pintype "passive"))
      (node (ref "C160") (pin "2") (pinfunction "2_2") (pintype "passive"))
      (node (ref "C161") (pin "2") (pinfunction "2_2") (pintype "passive"))
      (node (ref "C162") (pin "2") (pinfunction "2_2") (pintype "passive"))
      (node (ref "C163") (pin "2") (pinfunction "2_2") (pintype "passive"))
      (node (ref "C164") (pin "2") (pinfunction "2_2") (pintype "passive"))
      (node (ref "C174") (pin "2") (pinfunction "2_2") (pintype "passive"))
      (node (ref "IC4") (pin "H12") (pinfunction "VCCAUX_H12") (pintype "power_in"))
      (node (ref "IC4") (pin "K12") (pinfunction "VCCAUX_K12") (pintype "power_in"))
      (node (ref "IC4") (pin "M12") (pinfunction "VCCAUX_M12") (pintype "power_in"))
      (node (ref "IC4") (pin "P12") (pinfunction "VCCAUX_P12") (pintype "power_in"))
      (node (ref "IC4") (pin "R11") (pinfunction "VCCAUX_R11") (pintype "power_in"))
      (node (ref "L5") (pin "2") (pinfunction "2_2") (pintype "passive"))
    )
    (net (code "27") (name "VCCBRAM") (class "Default")
      (node (ref "C110") (pin "2") (pinfunction "2_2") (pintype "passive"))
      (node (ref "C112") (pin "2") (pinfunction "2_2") (pintype "passive"))
      (node (ref "C113") (pin "2") (pinfunction "2_2") (pintype "passive"))
      (node (ref "C320") (pin "2") (pinfunction "2_2") (pintype "passive"))
      (node (ref "IC4") (pin "J11") (pinfunction "VCCBRAM_J11") (pintype "power_in"))
      (node (ref "IC4") (pin "L11") (pinfunction "VCCBRAM_L11") (pintype "power_in"))
      (node (ref "IC4") (pin "N11") (pinfunction "VCCBRAM_N11") (pintype "power_in"))
    )
  )
)
